# cw312_xc7A35t_fpga_io1.net
KiCad netlist of a schematic drawn in Altium Designer
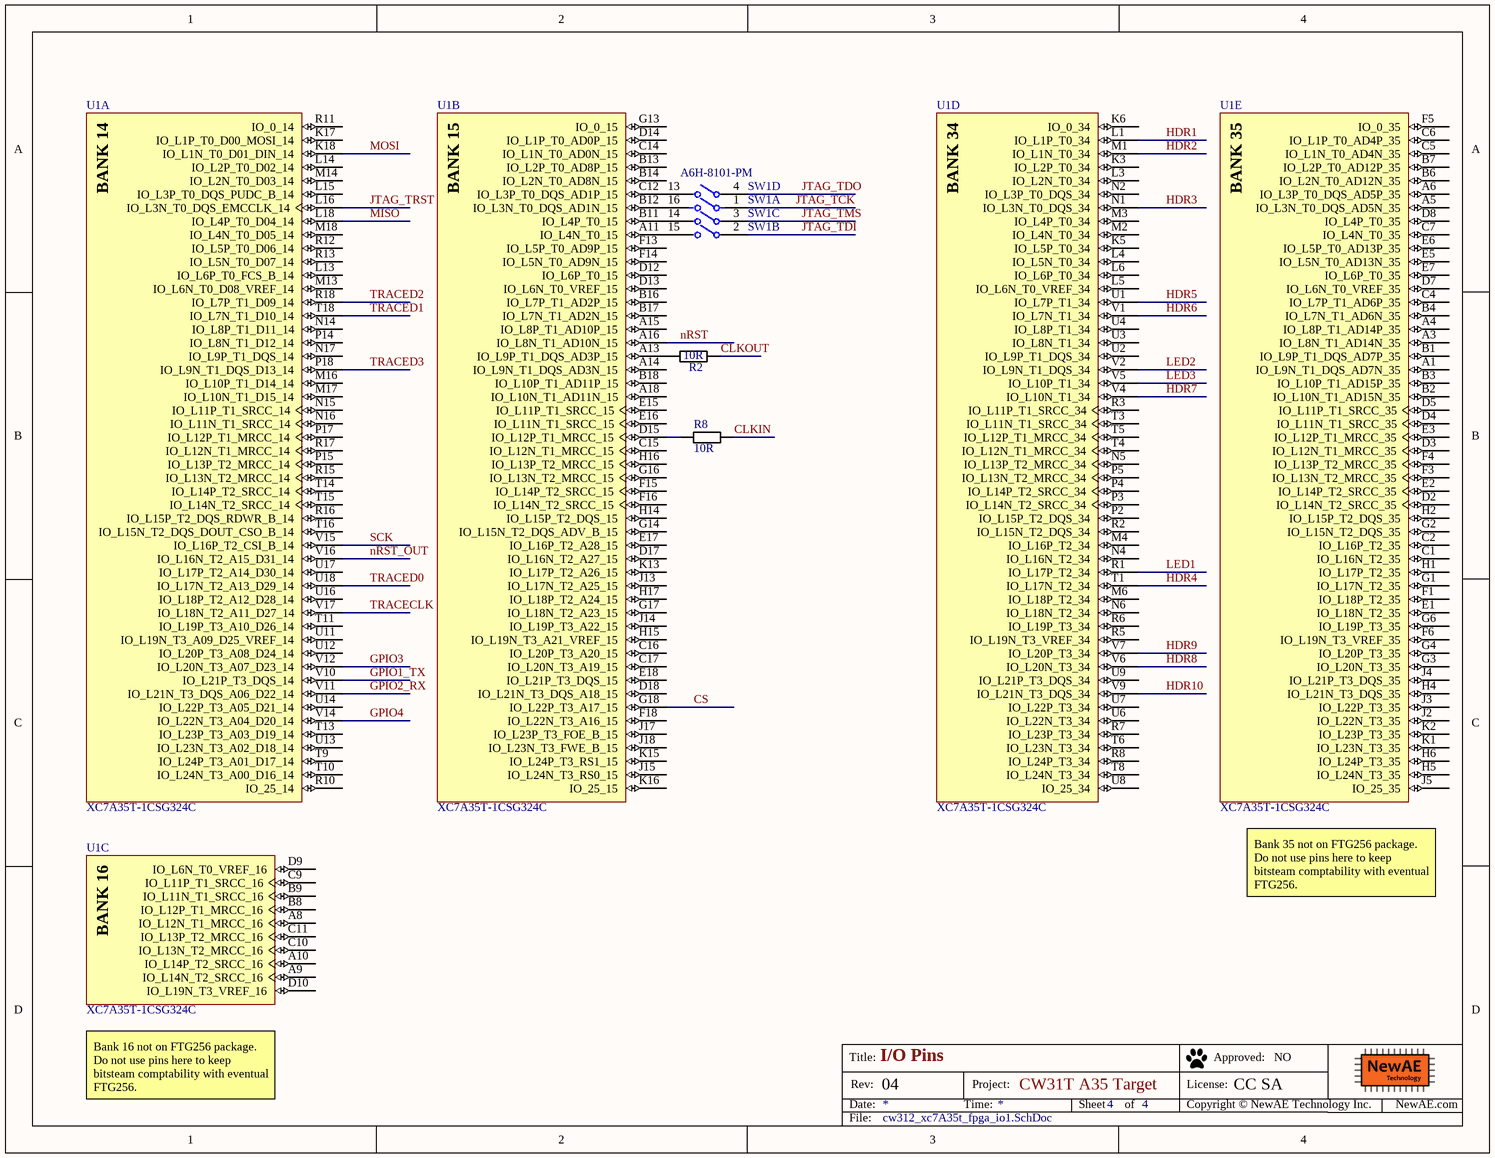
[diagram p0: cw312_xc7A35t_fpga_io1.SchDoc]

(export (version "E")
  (design (tool "Eeschema 10.0.6"))
  (components
    (comp (ref "R2")
      (value "10R")
      (footprint "RESC1608X55N")
      (description "10R res, 0603, 1%, 1/10W")
      (fields (field (name "PART NUMBER") "RCHIP-10R-0603") (field (name "TOLERANCE") "1%"))
      (libsource (lib "NewAE_AltiumLib") (part "RES-EU"))
    )
    (comp (ref "R8")
      (value "10R")
      (footprint "RESC1608X55N")
      (description "10R res, 0603, 1%, 1/10W")
      (fields (field (name "PART NUMBER") "RCHIP-10R-0603") (field (name "TOLERANCE") "1%"))
      (libsource (lib "NewAE_AltiumLib") (part "RES-EU"))
    )
    (comp (ref "SW1")
      (value "A6H-8101-PM")
      (footprint "FP-A6H-8101-PM-MFG")
      (description "SWITCH SLIDE DIP SPST 25MA 24V")
      (libsource (lib "Altium Content Vault") (part "b1c630a2f26d6f55c46b66680387f8a"))
    )
    (comp (ref "U1")
      (value "XC7A35T-1CSG324C")
      (footprint "CSG324")
      (description "Artix-7 FPGA, 210 User I/Os, 0 GTP, 324-Ball BGA, Speed Grade 1, Commercial Grade, Pb-Free")
      (fields (field (name "MANUFACTURER") "Xilinx"))
      (libsource (lib "Altium Content Vault") (part "XLNX-XC7A35T-CSG324"))
    )
  )
  (nets
    (net (code "1") (name "/CLKIN") (class "Default")
      (node (ref "R8") (pin "1") (pinfunction "1_1") (pintype "passive"))
    )
    (net (code "2") (name "/CLKOUT") (class "Default")
      (node (ref "R2") (pin "1") (pinfunction "1_1") (pintype "passive"))
    )
    (net (code "3") (name "/CS") (class "Default")
      (node (ref "U1") (pin "G18") (pinfunction "IO_L22P_T3_A17_15_G18") (pintype "bidirectional"))
    )
    (net (code "4") (name "/GPIO1_TX") (class "Default")
      (node (ref "U1") (pin "V10") (pinfunction "IO_L21P_T3_DQS_14_V10") (pintype "bidirectional"))
    )
    (net (code "5") (name "/GPIO2_RX") (class "Default")
      (node (ref "U1") (pin "V11") (pinfunction "IO_L21N_T3_DQS_A06_D22_14_V11") (pintype "bidirectional"))
    )
    (net (code "6") (name "/GPIO3") (class "Default")
      (node (ref "U1") (pin "V12") (pinfunction "IO_L20N_T3_A07_D23_14_V12") (pintype "bidirectional"))
    )
    (net (code "7") (name "/GPIO4") (class "Default")
      (node (ref "U1") (pin "V14") (pinfunction "IO_L22N_T3_A04_D20_14_V14") (pintype "bidirectional"))
    )
    (net (code "8") (name "/HDR1") (class "Default")
      (node (ref "U1") (pin "L1") (pinfunction "IO_L1P_T0_34_L1") (pintype "bidirectional"))
    )
    (net (code "9") (name "/HDR2") (class "Default")
      (node (ref "U1") (pin "M1") (pinfunction "IO_L1N_T0_34_M1") (pintype "bidirectional"))
    )
    (net (code "10") (name "/HDR3") (class "Default")
      (node (ref "U1") (pin "N1") (pinfunction "IO_L3N_T0_DQS_34_N1") (pintype "bidirectional"))
    )
    (net (code "11") (name "/HDR4") (class "Default")
      (node (ref "U1") (pin "T1") (pinfunction "IO_L17N_T2_34_T1") (pintype "bidirectional"))
    )
    (net (code "12") (name "/HDR5") (class "Default")
      (node (ref "U1") (pin "U1") (pinfunction "IO_L7P_T1_34_U1") (pintype "bidirectional"))
    )
    (net (code "13") (name "/HDR6") (class "Default")
      (node (ref "U1") (pin "V1") (pinfunction "IO_L7N_T1_34_V1") (pintype "bidirectional"))
    )
    (net (code "14") (name "/HDR7") (class "Default")
      (node (ref "U1") (pin "V4") (pinfunction "IO_L10N_T1_34_V4") (pintype "bidirectional"))
    )
    (net (code "15") (name "/HDR8") (class "Default")
      (node (ref "U1") (pin "V6") (pinfunction "IO_L20N_T3_34_V6") (pintype "bidirectional"))
    )
    (net (code "16") (name "/HDR9") (class "Default")
      (node (ref "U1") (pin "V7") (pinfunction "IO_L20P_T3_34_V7") (pintype "bidirectional"))
    )
    (net (code "17") (name "/HDR10") (class "Default")
      (node (ref "U1") (pin "V9") (pinfunction "IO_L21N_T3_DQS_34_V9") (pintype "bidirectional"))
    )
    (net (code "18") (name "/JTAG_TCK") (class "Default")
      (node (ref "SW1") (pin "1") (pinfunction "1_1") (pintype "passive"))
    )
    (net (code "19") (name "/JTAG_TDI") (class "Default")
      (node (ref "SW1") (pin "2") (pinfunction "2_2") (pintype "passive"))
    )
    (net (code "20") (name "/JTAG_TDO") (class "Default")
      (node (ref "SW1") (pin "4") (pinfunction "4_4") (pintype "passive"))
    )
    (net (code "21") (name "/JTAG_TMS") (class "Default")
      (node (ref "SW1") (pin "3") (pinfunction "3_3") (pintype "passive"))
    )
    (net (code "22") (name "/JTAG_TRST") (class "Default")
      (node (ref "U1") (pin "L16") (pinfunction "IO_L3N_T0_DQS_EMCCLK_14_L16") (pintype "bidirectional"))
    )
    (net (code "23") (name "/LED1") (class "Default")
      (node (ref "U1") (pin "R1") (pinfunction "IO_L17P_T2_34_R1") (pintype "bidirectional"))
    )
    (net (code "24") (name "/LED2") (class "Default")
      (node (ref "U1") (pin "V2") (pinfunction "IO_L9N_T1_DQS_34_V2") (pintype "bidirectional"))
    )
    (net (code "25") (name "/LED3") (class "Default")
      (node (ref "U1") (pin "V5") (pinfunction "IO_L10P_T1_34_V5") (pintype "bidirectional"))
    )
    (net (code "26") (name "/MISO") (class "Default")
      (node (ref "U1") (pin "L18") (pinfunction "IO_L4P_T0_D04_14_L18") (pintype "bidirectional"))
    )
    (net (code "27") (name "/MOSI") (class "Default")
      (node (ref "U1") (pin "K18") (pinfunction "IO_L1N_T0_D01_DIN_14_K18") (pintype "bidirectional"))
    )
    (net (code "28") (name "/SCK") (class "Default")
      (node (ref "U1") (pin "V15") (pinfunction "IO_L16P_T2_CSI_B_14_V15") (pintype "bidirectional"))
    )
    (net (code "29") (name "/TRACECLK") (class "Default")
      (node (ref "U1") (pin "V17") (pinfunction "IO_L18N_T2_A11_D27_14_V17") (pintype "bidirectional"))
    )
    (net (code "30") (name "/TRACED0") (class "Default")
      (node (ref "U1") (pin "U18") (pinfunction "IO_L17N_T2_A13_D29_14_U18") (pintype "bidirectional"))
    )
    (net (code "31") (name "/TRACED1") (class "Default")
      (node (ref "U1") (pin "T18") (pinfunction "IO_L7N_T1_D10_14_T18") (pintype "bidirectional"))
    )
    (net (code "32") (name "/TRACED2") (class "Default")
      (node (ref "U1") (pin "R18") (pinfunction "IO_L7P_T1_D09_14_R18") (pintype "bidirectional"))
    )
    (net (code "33") (name "/TRACED3") (class "Default")
      (node (ref "U1") (pin "P18") (pinfunction "IO_L9N_T1_DQS_D13_14_P18") (pintype "bidirectional"))
    )
    (net (code "34") (name "/nRST") (class "Default")
      (node (ref "U1") (pin "A16") (pinfunction "IO_L8N_T1_AD10N_15_A16") (pintype "bidirectional"))
    )
    (net (code "35") (name "/nRST_OUT") (class "Default")
      (node (ref "U1") (pin "V16") (pinfunction "IO_L16N_T2_A15_D31_14_V16") (pintype "bidirectional"))
    )
    (net (code "36") (name "Net-(U1B-IO_L3N_T0_DQS_AD1N_15)") (class "Default")
      (node (ref "SW1") (pin "16") (pinfunction "16_16") (pintype "passive"))
      (node (ref "U1") (pin "B12") (pinfunction "IO_L3N_T0_DQS_AD1N_15_B12") (pintype "bidirectional"))
    )
    (net (code "37") (name "Net-(U1B-IO_L3P_T0_DQS_AD1P_15)") (class "Default")
      (node (ref "SW1") (pin "13") (pinfunction "13_13") (pintype "passive"))
      (node (ref "U1") (pin "C12") (pinfunction "IO_L3P_T0_DQS_AD1P_15_C12") (pintype "bidirectional"))
    )
    (net (code "38") (name "Net-(U1B-IO_L4N_T0_15)") (class "Default")
      (node (ref "SW1") (pin "15") (pinfunction "15_15") (pintype "passive"))
      (node (ref "U1") (pin "A11") (pinfunction "IO_L4N_T0_15_A11") (pintype "bidirectional"))
    )
    (net (code "39") (name "Net-(U1B-IO_L4P_T0_15)") (class "Default")
      (node (ref "SW1") (pin "14") (pinfunction "14_14") (pintype "passive"))
      (node (ref "U1") (pin "B11") (pinfunction "IO_L4P_T0_15_B11") (pintype "bidirectional"))
    )
    (net (code "40") (name "Net-(U1B-IO_L9P_T1_DQS_AD3P_15)") (class "Default")
      (node (ref "R2") (pin "2") (pinfunction "2_2") (pintype "passive"))
      (node (ref "U1") (pin "A13") (pinfunction "IO_L9P_T1_DQS_AD3P_15_A13") (pintype "bidirectional"))
    )
    (net (code "41") (name "Net-(U1B-IO_L12P_T1_MRCC_15)") (class "Default")
      (node (ref "R8") (pin "2") (pinfunction "2_2") (pintype "passive"))
      (node (ref "U1") (pin "D15") (pinfunction "IO_L12P_T1_MRCC_15_D15") (pintype "bidirectional"))
    )
    (net (code "42") (name "unconnected-(U1A-IO_0_14-PadR11)") (class "Default")
      (node (ref "U1") (pin "R11") (pinfunction "IO_0_14_R11") (pintype "bidirectional"))
    )
    (net (code "43") (name "unconnected-(U1A-IO_25_14-PadR10)") (class "Default")
      (node (ref "U1") (pin "R10") (pinfunction "IO_25_14_R10") (pintype "bidirectional"))
    )
    (net (code "44") (name "unconnected-(U1A-IO_L1P_T0_D00_MOSI_14-PadK17)") (class "Default")
      (node (ref "U1") (pin "K17") (pinfunction "IO_L1P_T0_D00_MOSI_14_K17") (pintype "bidirectional"))
    )
    (net (code "45") (name "unconnected-(U1A-IO_L2N_T0_D03_14-PadM14)") (class "Default")
      (node (ref "U1") (pin "M14") (pinfunction "IO_L2N_T0_D03_14_M14") (pintype "bidirectional"))
    )
    (net (code "46") (name "unconnected-(U1A-IO_L2P_T0_D02_14-PadL14)") (class "Default")
      (node (ref "U1") (pin "L14") (pinfunction "IO_L2P_T0_D02_14_L14") (pintype "bidirectional"))
    )
    (net (code "47") (name "unconnected-(U1A-IO_L3P_T0_DQS_PUDC_B_14-PadL15)") (class "Default")
      (node (ref "U1") (pin "L15") (pinfunction "IO_L3P_T0_DQS_PUDC_B_14_L15") (pintype "bidirectional"))
    )
    (net (code "48") (name "unconnected-(U1A-IO_L4N_T0_D05_14-PadM18)") (class "Default")
      (node (ref "U1") (pin "M18") (pinfunction "IO_L4N_T0_D05_14_M18") (pintype "bidirectional"))
    )
    (net (code "49") (name "unconnected-(U1A-IO_L5N_T0_D07_14-PadR13)") (class "Default")
      (node (ref "U1") (pin "R13") (pinfunction "IO_L5N_T0_D07_14_R13") (pintype "bidirectional"))
    )
    (net (code "50") (name "unconnected-(U1A-IO_L5P_T0_D06_14-PadR12)") (class "Default")
      (node (ref "U1") (pin "R12") (pinfunction "IO_L5P_T0_D06_14_R12") (pintype "bidirectional"))
    )
    (net (code "51") (name "unconnected-(U1A-IO_L6N_T0_D08_VREF_14-PadM13)") (class "Default")
      (node (ref "U1") (pin "M13") (pinfunction "IO_L6N_T0_D08_VREF_14_M13") (pintype "bidirectional"))
    )
    (net (code "52") (name "unconnected-(U1A-IO_L6P_T0_FCS_B_14-PadL13)") (class "Default")
      (node (ref "U1") (pin "L13") (pinfunction "IO_L6P_T0_FCS_B_14_L13") (pintype "bidirectional"))
    )
    (net (code "53") (name "unconnected-(U1A-IO_L8N_T1_D12_14-PadP14)") (class "Default")
      (node (ref "U1") (pin "P14") (pinfunction "IO_L8N_T1_D12_14_P14") (pintype "bidirectional"))
    )
    (net (code "54") (name "unconnected-(U1A-IO_L8P_T1_D11_14-PadN14)") (class "Default")
      (node (ref "U1") (pin "N14") (pinfunction "IO_L8P_T1_D11_14_N14") (pintype "bidirectional"))
    )
    (net (code "55") (name "unconnected-(U1A-IO_L9P_T1_DQS_14-PadN17)") (class "Default")
      (node (ref "U1") (pin "N17") (pinfunction "IO_L9P_T1_DQS_14_N17") (pintype "bidirectional"))
    )
    (net (code "56") (name "unconnected-(U1A-IO_L10N_T1_D15_14-PadM17)") (class "Default")
      (node (ref "U1") (pin "M17") (pinfunction "IO_L10N_T1_D15_14_M17") (pintype "bidirectional"))
    )
    (net (code "57") (name "unconnected-(U1A-IO_L10P_T1_D14_14-PadM16)") (class "Default")
      (node (ref "U1") (pin "M16") (pinfunction "IO_L10P_T1_D14_14_M16") (pintype "bidirectional"))
    )
    (net (code "58") (name "unconnected-(U1A-IO_L11N_T1_SRCC_14-PadN16)") (class "Default")
      (node (ref "U1") (pin "N16") (pinfunction "IO_L11N_T1_SRCC_14_N16") (pintype "bidirectional"))
    )
    (net (code "59") (name "unconnected-(U1A-IO_L11P_T1_SRCC_14-PadN15)") (class "Default")
      (node (ref "U1") (pin "N15") (pinfunction "IO_L11P_T1_SRCC_14_N15") (pintype "bidirectional"))
    )
    (net (code "60") (name "unconnected-(U1A-IO_L12N_T1_MRCC_14-PadR17)") (class "Default")
      (node (ref "U1") (pin "R17") (pinfunction "IO_L12N_T1_MRCC_14_R17") (pintype "bidirectional"))
    )
    (net (code "61") (name "unconnected-(U1A-IO_L12P_T1_MRCC_14-PadP17)") (class "Default")
      (node (ref "U1") (pin "P17") (pinfunction "IO_L12P_T1_MRCC_14_P17") (pintype "bidirectional"))
    )
    (net (code "62") (name "unconnected-(U1A-IO_L13N_T2_MRCC_14-PadR15)") (class "Default")
      (node (ref "U1") (pin "R15") (pinfunction "IO_L13N_T2_MRCC_14_R15") (pintype "bidirectional"))
    )
    (net (code "63") (name "unconnected-(U1A-IO_L13P_T2_MRCC_14-PadP15)") (class "Default")
      (node (ref "U1") (pin "P15") (pinfunction "IO_L13P_T2_MRCC_14_P15") (pintype "bidirectional"))
    )
    (net (code "64") (name "unconnected-(U1A-IO_L14N_T2_SRCC_14-PadT15)") (class "Default")
      (node (ref "U1") (pin "T15") (pinfunction "IO_L14N_T2_SRCC_14_T15") (pintype "bidirectional"))
    )
    (net (code "65") (name "unconnected-(U1A-IO_L14P_T2_SRCC_14-PadT14)") (class "Default")
      (node (ref "U1") (pin "T14") (pinfunction "IO_L14P_T2_SRCC_14_T14") (pintype "bidirectional"))
    )
    (net (code "66") (name "unconnected-(U1A-IO_L15N_T2_DQS_DOUT_CSO_B_14-PadT16)") (class "Default")
      (node (ref "U1") (pin "T16") (pinfunction "IO_L15N_T2_DQS_DOUT_CSO_B_14_T16") (pintype "bidirectional"))
    )
    (net (code "67") (name "unconnected-(U1A-IO_L15P_T2_DQS_RDWR_B_14-PadR16)") (class "Default")
      (node (ref "U1") (pin "R16") (pinfunction "IO_L15P_T2_DQS_RDWR_B_14_R16") (pintype "bidirectional"))
    )
    (net (code "68") (name "unconnected-(U1A-IO_L17P_T2_A14_D30_14-PadU17)") (class "Default")
      (node (ref "U1") (pin "U17") (pinfunction "IO_L17P_T2_A14_D30_14_U17") (pintype "bidirectional"))
    )
    (net (code "69") (name "unconnected-(U1A-IO_L18P_T2_A12_D28_14-PadU16)") (class "Default")
      (node (ref "U1") (pin "U16") (pinfunction "IO_L18P_T2_A12_D28_14_U16") (pintype "bidirectional"))
    )
    (net (code "70") (name "unconnected-(U1A-IO_L19N_T3_A09_D25_VREF_14-PadU11)") (class "Default")
      (node (ref "U1") (pin "U11") (pinfunction "IO_L19N_T3_A09_D25_VREF_14_U11") (pintype "bidirectional"))
    )
    (net (code "71") (name "unconnected-(U1A-IO_L19P_T3_A10_D26_14-PadT11)") (class "Default")
      (node (ref "U1") (pin "T11") (pinfunction "IO_L19P_T3_A10_D26_14_T11") (pintype "bidirectional"))
    )
    (net (code "72") (name "unconnected-(U1A-IO_L20P_T3_A08_D24_14-PadU12)") (class "Default")
      (node (ref "U1") (pin "U12") (pinfunction "IO_L20P_T3_A08_D24_14_U12") (pintype "bidirectional"))
    )
    (net (code "73") (name "unconnected-(U1A-IO_L22P_T3_A05_D21_14-PadU14)") (class "Default")
      (node (ref "U1") (pin "U14") (pinfunction "IO_L22P_T3_A05_D21_14_U14") (pintype "bidirectional"))
    )
    (net (code "74") (name "unconnected-(U1A-IO_L23N_T3_A02_D18_14-PadU13)") (class "Default")
      (node (ref "U1") (pin "U13") (pinfunction "IO_L23N_T3_A02_D18_14_U13") (pintype "bidirectional"))
    )
    (net (code "75") (name "unconnected-(U1A-IO_L23P_T3_A03_D19_14-PadT13)") (class "Default")
      (node (ref "U1") (pin "T13") (pinfunction "IO_L23P_T3_A03_D19_14_T13") (pintype "bidirectional"))
    )
    (net (code "76") (name "unconnected-(U1A-IO_L24N_T3_A00_D16_14-PadT10)") (class "Default")
      (node (ref "U1") (pin "T10") (pinfunction "IO_L24N_T3_A00_D16_14_T10") (pintype "bidirectional"))
    )
    (net (code "77") (name "unconnected-(U1A-IO_L24P_T3_A01_D17_14-PadT9)") (class "Default")
      (node (ref "U1") (pin "T9") (pinfunction "IO_L24P_T3_A01_D17_14_T9") (pintype "bidirectional"))
    )
    (net (code "78") (name "unconnected-(U1B-IO_0_15-PadG13)") (class "Default")
      (node (ref "U1") (pin "G13") (pinfunction "IO_0_15_G13") (pintype "bidirectional"))
    )
    (net (code "79") (name "unconnected-(U1B-IO_25_15-PadK16)") (class "Default")
      (node (ref "U1") (pin "K16") (pinfunction "IO_25_15_K16") (pintype "bidirectional"))
    )
    (net (code "80") (name "unconnected-(U1B-IO_L1N_T0_AD0N_15-PadC14)") (class "Default")
      (node (ref "U1") (pin "C14") (pinfunction "IO_L1N_T0_AD0N_15_C14") (pintype "bidirectional"))
    )
    (net (code "81") (name "unconnected-(U1B-IO_L1P_T0_AD0P_15-PadD14)") (class "Default")
      (node (ref "U1") (pin "D14") (pinfunction "IO_L1P_T0_AD0P_15_D14") (pintype "bidirectional"))
    )
    (net (code "82") (name "unconnected-(U1B-IO_L2N_T0_AD8N_15-PadB14)") (class "Default")
      (node (ref "U1") (pin "B14") (pinfunction "IO_L2N_T0_AD8N_15_B14") (pintype "bidirectional"))
    )
    (net (code "83") (name "unconnected-(U1B-IO_L2P_T0_AD8P_15-PadB13)") (class "Default")
      (node (ref "U1") (pin "B13") (pinfunction "IO_L2P_T0_AD8P_15_B13") (pintype "bidirectional"))
    )
    (net (code "84") (name "unconnected-(U1B-IO_L5N_T0_AD9N_15-PadF14)") (class "Default")
      (node (ref "U1") (pin "F14") (pinfunction "IO_L5N_T0_AD9N_15_F14") (pintype "bidirectional"))
    )
    (net (code "85") (name "unconnected-(U1B-IO_L5P_T0_AD9P_15-PadF13)") (class "Default")
      (node (ref "U1") (pin "F13") (pinfunction "IO_L5P_T0_AD9P_15_F13") (pintype "bidirectional"))
    )
    (net (code "86") (name "unconnected-(U1B-IO_L6N_T0_VREF_15-PadD13)") (class "Default")
      (node (ref "U1") (pin "D13") (pinfunction "IO_L6N_T0_VREF_15_D13") (pintype "bidirectional"))
    )
    (net (code "87") (name "unconnected-(U1B-IO_L6P_T0_15-PadD12)") (class "Default")
      (node (ref "U1") (pin "D12") (pinfunction "IO_L6P_T0_15_D12") (pintype "bidirectional"))
    )
    (net (code "88") (name "unconnected-(U1B-IO_L7N_T1_AD2N_15-PadB17)") (class "Default")
      (node (ref "U1") (pin "B17") (pinfunction "IO_L7N_T1_AD2N_15_B17") (pintype "bidirectional"))
    )
    (net (code "89") (name "unconnected-(U1B-IO_L7P_T1_AD2P_15-PadB16)") (class "Default")
      (node (ref "U1") (pin "B16") (pinfunction "IO_L7P_T1_AD2P_15_B16") (pintype "bidirectional"))
    )
    (net (code "90") (name "unconnected-(U1B-IO_L8P_T1_AD10P_15-PadA15)") (class "Default")
      (node (ref "U1") (pin "A15") (pinfunction "IO_L8P_T1_AD10P_15_A15") (pintype "bidirectional"))
    )
    (net (code "91") (name "unconnected-(U1B-IO_L9N_T1_DQS_AD3N_15-PadA14)") (class "Default")
      (node (ref "U1") (pin "A14") (pinfunction "IO_L9N_T1_DQS_AD3N_15_A14") (pintype "bidirectional"))
    )
    (net (code "92") (name "unconnected-(U1B-IO_L10N_T1_AD11N_15-PadA18)") (class "Default")
      (node (ref "U1") (pin "A18") (pinfunction "IO_L10N_T1_AD11N_15_A18") (pintype "bidirectional"))
    )
    (net (code "93") (name "unconnected-(U1B-IO_L10P_T1_AD11P_15-PadB18)") (class "Default")
      (node (ref "U1") (pin "B18") (pinfunction "IO_L10P_T1_AD11P_15_B18") (pintype "bidirectional"))
    )
    (net (code "94") (name "unconnected-(U1B-IO_L11N_T1_SRCC_15-PadE16)") (class "Default")
      (node (ref "U1") (pin "E16") (pinfunction "IO_L11N_T1_SRCC_15_E16") (pintype "bidirectional"))
    )
    (net (code "95") (name "unconnected-(U1B-IO_L11P_T1_SRCC_15-PadE15)") (class "Default")
      (node (ref "U1") (pin "E15") (pinfunction "IO_L11P_T1_SRCC_15_E15") (pintype "bidirectional"))
    )
    (net (code "96") (name "unconnected-(U1B-IO_L12N_T1_MRCC_15-PadC15)") (class "Default")
      (node (ref "U1") (pin "C15") (pinfunction "IO_L12N_T1_MRCC_15_C15") (pintype "bidirectional"))
    )
    (net (code "97") (name "unconnected-(U1B-IO_L13N_T2_MRCC_15-PadG16)") (class "Default")
      (node (ref "U1") (pin "G16") (pinfunction "IO_L13N_T2_MRCC_15_G16") (pintype "bidirectional"))
    )
    (net (code "98") (name "unconnected-(U1B-IO_L13P_T2_MRCC_15-PadH16)") (class "Default")
      (node (ref "U1") (pin "H16") (pinfunction "IO_L13P_T2_MRCC_15_H16") (pintype "bidirectional"))
    )
    (net (code "99") (name "unconnected-(U1B-IO_L14N_T2_SRCC_15-PadF16)") (class "Default")
      (node (ref "U1") (pin "F16") (pinfunction "IO_L14N_T2_SRCC_15_F16") (pintype "bidirectional"))
    )
    (net (code "100") (name "unconnected-(U1B-IO_L14P_T2_SRCC_15-PadF15)") (class "Default")
      (node (ref "U1") (pin "F15") (pinfunction "IO_L14P_T2_SRCC_15_F15") (pintype "bidirectional"))
    )
    (net (code "101") (name "unconnected-(U1B-IO_L15N_T2_DQS_ADV_B_15-PadG14)") (class "Default")
      (node (ref "U1") (pin "G14") (pinfunction "IO_L15N_T2_DQS_ADV_B_15_G14") (pintype "bidirectional"))
    )
    (net (code "102") (name "unconnected-(U1B-IO_L15P_T2_DQS_15-PadH14)") (class "Default")
      (node (ref "U1") (pin "H14") (pinfunction "IO_L15P_T2_DQS_15_H14") (pintype "bidirectional"))
    )
    (net (code "103") (name "unconnected-(U1B-IO_L16N_T2_A27_15-PadD17)") (class "Default")
      (node (ref "U1") (pin "D17") (pinfunction "IO_L16N_T2_A27_15_D17") (pintype "bidirectional"))
    )
    (net (code "104") (name "unconnected-(U1B-IO_L16P_T2_A28_15-PadE17)") (class "Default")
      (node (ref "U1") (pin "E17") (pinfunction "IO_L16P_T2_A28_15_E17") (pintype "bidirectional"))
    )
    (net (code "105") (name "unconnected-(U1B-IO_L17N_T2_A25_15-PadJ13)") (class "Default")
      (node (ref "U1") (pin "J13") (pinfunction "IO_L17N_T2_A25_15_J13") (pintype "bidirectional"))
    )
    (net (code "106") (name "unconnected-(U1B-IO_L17P_T2_A26_15-PadK13)") (class "Default")
      (node (ref "U1") (pin "K13") (pinfunction "IO_L17P_T2_A26_15_K13") (pintype "bidirectional"))
    )
    (net (code "107") (name "unconnected-(U1B-IO_L18N_T2_A23_15-PadG17)") (class "Default")
      (node (ref "U1") (pin "G17") (pinfunction "IO_L18N_T2_A23_15_G17") (pintype "bidirectional"))
    )
    (net (code "108") (name "unconnected-(U1B-IO_L18P_T2_A24_15-PadH17)") (class "Default")
      (node (ref "U1") (pin "H17") (pinfunction "IO_L18P_T2_A24_15_H17") (pintype "bidirectional"))
    )
    (net (code "109") (name "unconnected-(U1B-IO_L19N_T3_A21_VREF_15-PadH15)") (class "Default")
      (node (ref "U1") (pin "H15") (pinfunction "IO_L19N_T3_A21_VREF_15_H15") (pintype "bidirectional"))
    )
    (net (code "110") (name "unconnected-(U1B-IO_L19P_T3_A22_15-PadJ14)") (class "Default")
      (node (ref "U1") (pin "J14") (pinfunction "IO_L19P_T3_A22_15_J14") (pintype "bidirectional"))
    )
    (net (code "111") (name "unconnected-(U1B-IO_L20N_T3_A19_15-PadC17)") (class "Default")
      (node (ref "U1") (pin "C17") (pinfunction "IO_L20N_T3_A19_15_C17") (pintype "bidirectional"))
    )
    (net (code "112") (name "unconnected-(U1B-IO_L20P_T3_A20_15-PadC16)") (class "Default")
      (node (ref "U1") (pin "C16") (pinfunction "IO_L20P_T3_A20_15_C16") (pintype "bidirectional"))
    )
    (net (code "113") (name "unconnected-(U1B-IO_L21N_T3_DQS_A18_15-PadD18)") (class "Default")
      (node (ref "U1") (pin "D18") (pinfunction "IO_L21N_T3_DQS_A18_15_D18") (pintype "bidirectional"))
    )
    (net (code "114") (name "unconnected-(U1B-IO_L21P_T3_DQS_15-PadE18)") (class "Default")
      (node (ref "U1") (pin "E18") (pinfunction "IO_L21P_T3_DQS_15_E18") (pintype "bidirectional"))
    )
    (net (code "115") (name "unconnected-(U1B-IO_L22N_T3_A16_15-PadF18)") (class "Default")
      (node (ref "U1") (pin "F18") (pinfunction "IO_L22N_T3_A16_15_F18") (pintype "bidirectional"))
    )
    (net (code "116") (name "unconnected-(U1B-IO_L23N_T3_FWE_B_15-PadJ18)") (class "Default")
      (node (ref "U1") (pin "J18") (pinfunction "IO_L23N_T3_FWE_B_15_J18") (pintype "bidirectional"))
    )
    (net (code "117") (name "unconnected-(U1B-IO_L23P_T3_FOE_B_15-PadJ17)") (class "Default")
      (node (ref "U1") (pin "J17") (pinfunction "IO_L23P_T3_FOE_B_15_J17") (pintype "bidirectional"))
    )
    (net (code "118") (name "unconnected-(U1B-IO_L24N_T3_RS0_15-PadJ15)") (class "Default")
      (node (ref "U1") (pin "J15") (pinfunction "IO_L24N_T3_RS0_15_J15") (pintype "bidirectional"))
    )
    (net (code "119") (name "unconnected-(U1B-IO_L24P_T3_RS1_15-PadK15)") (class "Default")
      (node (ref "U1") (pin "K15") (pinfunction "IO_L24P_T3_RS1_15_K15") (pintype "bidirectional"))
    )
    (net (code "120") (name "unconnected-(U1C-IO_L6N_T0_VREF_16-PadD9)") (class "Default")
      (node (ref "U1") (pin "D9") (pinfunction "IO_L6N_T0_VREF_16_D9") (pintype "bidirectional"))
    )
    (net (code "121") (name "unconnected-(U1C-IO_L11N_T1_SRCC_16-PadB9)") (class "Default")
      (node (ref "U1") (pin "B9") (pinfunction "IO_L11N_T1_SRCC_16_B9") (pintype "bidirectional"))
    )
    (net (code "122") (name "unconnected-(U1C-IO_L11P_T1_SRCC_16-PadC9)") (class "Default")
      (node (ref "U1") (pin "C9") (pinfunction "IO_L11P_T1_SRCC_16_C9") (pintype "bidirectional"))
    )
    (net (code "123") (name "unconnected-(U1C-IO_L12N_T1_MRCC_16-PadA8)") (class "Default")
      (node (ref "U1") (pin "A8") (pinfunction "IO_L12N_T1_MRCC_16_A8") (pintype "bidirectional"))
    )
    (net (code "124") (name "unconnected-(U1C-IO_L12P_T1_MRCC_16-PadB8)") (class "Default")
      (node (ref "U1") (pin "B8") (pinfunction "IO_L12P_T1_MRCC_16_B8") (pintype "bidirectional"))
    )
    (net (code "125") (name "unconnected-(U1C-IO_L13N_T2_MRCC_16-PadC10)") (class "Default")
      (node (ref "U1") (pin "C10") (pinfunction "IO_L13N_T2_MRCC_16_C10") (pintype "bidirectional"))
    )
    (net (code "126") (name "unconnected-(U1C-IO_L13P_T2_MRCC_16-PadC11)") (class "Default")
      (node (ref "U1") (pin "C11") (pinfunction "IO_L13P_T2_MRCC_16_C11") (pintype "bidirectional"))
    )
    (net (code "127") (name "unconnected-(U1C-IO_L14N_T2_SRCC_16-PadA9)") (class "Default")
      (node (ref "U1") (pin "A9") (pinfunction "IO_L14N_T2_SRCC_16_A9") (pintype "bidirectional"))
    )
    (net (code "128") (name "unconnected-(U1C-IO_L14P_T2_SRCC_16-PadA10)") (class "Default")
      (node (ref "U1") (pin "A10") (pinfunction "IO_L14P_T2_SRCC_16_A10") (pintype "bidirectional"))
    )
    (net (code "129") (name "unconnected-(U1C-IO_L19N_T3_VREF_16-PadD10)") (class "Default")
      (node (ref "U1") (pin "D10") (pinfunction "IO_L19N_T3_VREF_16_D10") (pintype "bidirectional"))
    )
    (net (code "130") (name "unconnected-(U1D-IO_0_34-PadK6)") (class "Default")
      (node (ref "U1") (pin "K6") (pinfunction "IO_0_34_K6") (pintype "bidirectional"))
    )
    (net (code "131") (name "unconnected-(U1D-IO_25_34-PadU8)") (class "Default")
      (node (ref "U1") (pin "U8") (pinfunction "IO_25_34_U8") (pintype "bidirectional"))
    )
    (net (code "132") (name "unconnected-(U1D-IO_L2N_T0_34-PadL3)") (class "Default")
      (node (ref "U1") (pin "L3") (pinfunction "IO_L2N_T0_34_L3") (pintype "bidirectional"))
    )
    (net (code "133") (name "unconnected-(U1D-IO_L2P_T0_34-PadK3)") (class "Default")
      (node (ref "U1") (pin "K3") (pinfunction "IO_L2P_T0_34_K3") (pintype "bidirectional"))
    )
    (net (code "134") (name "unconnected-(U1D-IO_L3P_T0_DQS_34-PadN2)") (class "Default")
      (node (ref "U1") (pin "N2") (pinfunction "IO_L3P_T0_DQS_34_N2") (pintype "bidirectional"))
    )
    (net (code "135") (name "unconnected-(U1D-IO_L4N_T0_34-PadM2)") (class "Default")
      (node (ref "U1") (pin "M2") (pinfunction "IO_L4N_T0_34_M2") (pintype "bidirectional"))
    )
    (net (code "136") (name "unconnected-(U1D-IO_L4P_T0_34-PadM3)") (class "Default")
      (node (ref "U1") (pin "M3") (pinfunction "IO_L4P_T0_34_M3") (pintype "bidirectional"))
    )
    (net (code "137") (name "unconnected-(U1D-IO_L5N_T0_34-PadL4)") (class "Default")
      (node (ref "U1") (pin "L4") (pinfunction "IO_L5N_T0_34_L4") (pintype "bidirectional"))
    )
    (net (code "138") (name "unconnected-(U1D-IO_L5P_T0_34-PadK5)") (class "Default")
      (node (ref "U1") (pin "K5") (pinfunction "IO_L5P_T0_34_K5") (pintype "bidirectional"))
    )
    (net (code "139") (name "unconnected-(U1D-IO_L6N_T0_VREF_34-PadL5)") (class "Default")
      (node (ref "U1") (pin "L5") (pinfunction "IO_L6N_T0_VREF_34_L5") (pintype "bidirectional"))
    )
    (net (code "140") (name "unconnected-(U1D-IO_L6P_T0_34-PadL6)") (class "Default")
      (node (ref "U1") (pin "L6") (pinfunction "IO_L6P_T0_34_L6") (pintype "bidirectional"))
    )
    (net (code "141") (name "unconnected-(U1D-IO_L8N_T1_34-PadU3)") (class "Default")
      (node (ref "U1") (pin "U3") (pinfunction "IO_L8N_T1_34_U3") (pintype "bidirectional"))
    )
    (net (code "142") (name "unconnected-(U1D-IO_L8P_T1_34-PadU4)") (class "Default")
      (node (ref "U1") (pin "U4") (pinfunction "IO_L8P_T1_34_U4") (pintype "bidirectional"))
    )
    (net (code "143") (name "unconnected-(U1D-IO_L9P_T1_DQS_34-PadU2)") (class "Default")
      (node (ref "U1") (pin "U2") (pinfunction "IO_L9P_T1_DQS_34_U2") (pintype "bidirectional"))
    )
    (net (code "144") (name "unconnected-(U1D-IO_L11N_T1_SRCC_34-PadT3)") (class "Default")
      (node (ref "U1") (pin "T3") (pinfunction "IO_L11N_T1_SRCC_34_T3") (pintype "bidirectional"))
    )
    (net (code "145") (name "unconnected-(U1D-IO_L11P_T1_SRCC_34-PadR3)") (class "Default")
      (node (ref "U1") (pin "R3") (pinfunction "IO_L11P_T1_SRCC_34_R3") (pintype "bidirectional"))
    )
    (net (code "146") (name "unconnected-(U1D-IO_L12N_T1_MRCC_34-PadT4)") (class "Default")
      (node (ref "U1") (pin "T4") (pinfunction "IO_L12N_T1_MRCC_34_T4") (pintype "bidirectional"))
    )
    (net (code "147") (name "unconnected-(U1D-IO_L12P_T1_MRCC_34-PadT5)") (class "Default")
      (node (ref "U1") (pin "T5") (pinfunction "IO_L12P_T1_MRCC_34_T5") (pintype "bidirectional"))
    )
    (net (code "148") (name "unconnected-(U1D-IO_L13N_T2_MRCC_34-PadP5)") (class "Default")
      (node (ref "U1") (pin "P5") (pinfunction "IO_L13N_T2_MRCC_34_P5") (pintype "bidirectional"))
    )
    (net (code "149") (name "unconnected-(U1D-IO_L13P_T2_MRCC_34-PadN5)") (class "Default")
      (node (ref "U1") (pin "N5") (pinfunction "IO_L13P_T2_MRCC_34_N5") (pintype "bidirectional"))
    )
    (net (code "150") (name "unconnected-(U1D-IO_L14N_T2_SRCC_34-PadP3)") (class "Default")
      (node (ref "U1") (pin "P3") (pinfunction "IO_L14N_T2_SRCC_34_P3") (pintype "bidirectional"))
    )
    (net (code "151") (name "unconnected-(U1D-IO_L14P_T2_SRCC_34-PadP4)") (class "Default")
      (node (ref "U1") (pin "P4") (pinfunction "IO_L14P_T2_SRCC_34_P4") (pintype "bidirectional"))
    )
    (net (code "152") (name "unconnected-(U1D-IO_L15N_T2_DQS_34-PadR2)") (class "Default")
      (node (ref "U1") (pin "R2") (pinfunction "IO_L15N_T2_DQS_34_R2") (pintype "bidirectional"))
    )
    (net (code "153") (name "unconnected-(U1D-IO_L15P_T2_DQS_34-PadP2)") (class "Default")
      (node (ref "U1") (pin "P2") (pinfunction "IO_L15P_T2_DQS_34_P2") (pintype "bidirectional"))
    )
    (net (code "154") (name "unconnected-(U1D-IO_L16N_T2_34-PadN4)") (class "Default")
      (node (ref "U1") (pin "N4") (pinfunction "IO_L16N_T2_34_N4") (pintype "bidirectional"))
    )
    (net (code "155") (name "unconnected-(U1D-IO_L16P_T2_34-PadM4)") (class "Default")
      (node (ref "U1") (pin "M4") (pinfunction "IO_L16P_T2_34_M4") (pintype "bidirectional"))
    )
    (net (code "156") (name "unconnected-(U1D-IO_L18N_T2_34-PadN6)") (class "Default")
      (node (ref "U1") (pin "N6") (pinfunction "IO_L18N_T2_34_N6") (pintype "bidirectional"))
    )
    (net (code "157") (name "unconnected-(U1D-IO_L18P_T2_34-PadM6)") (class "Default")
      (node (ref "U1") (pin "M6") (pinfunction "IO_L18P_T2_34_M6") (pintype "bidirectional"))
    )
    (net (code "158") (name "unconnected-(U1D-IO_L19N_T3_VREF_34-PadR5)") (class "Default")
      (node (ref "U1") (pin "R5") (pinfunction "IO_L19N_T3_VREF_34_R5") (pintype "bidirectional"))
    )
    (net (code "159") (name "unconnected-(U1D-IO_L19P_T3_34-PadR6)") (class "Default")
      (node (ref "U1") (pin "R6") (pinfunction "IO_L19P_T3_34_R6") (pintype "bidirectional"))
    )
    (net (code "160") (name "unconnected-(U1D-IO_L21P_T3_DQS_34-PadU9)") (class "Default")
      (node (ref "U1") (pin "U9") (pinfunction "IO_L21P_T3_DQS_34_U9") (pintype "bidirectional"))
    )
    (net (code "161") (name "unconnected-(U1D-IO_L22N_T3_34-PadU6)") (class "Default")
      (node (ref "U1") (pin "U6") (pinfunction "IO_L22N_T3_34_U6") (pintype "bidirectional"))
    )
    (net (code "162") (name "unconnected-(U1D-IO_L22P_T3_34-PadU7)") (class "Default")
      (node (ref "U1") (pin "U7") (pinfunction "IO_L22P_T3_34_U7") (pintype "bidirectional"))
    )
    (net (code "163") (name "unconnected-(U1D-IO_L23N_T3_34-PadT6)") (class "Default")
      (node (ref "U1") (pin "T6") (pinfunction "IO_L23N_T3_34_T6") (pintype "bidirectional"))
    )
    (net (code "164") (name "unconnected-(U1D-IO_L23P_T3_34-PadR7)") (class "Default")
      (node (ref "U1") (pin "R7") (pinfunction "IO_L23P_T3_34_R7") (pintype "bidirectional"))
    )
    (net (code "165") (name "unconnected-(U1D-IO_L24N_T3_34-PadT8)") (class "Default")
      (node (ref "U1") (pin "T8") (pinfunction "IO_L24N_T3_34_T8") (pintype "bidirectional"))
    )
    (net (code "166") (name "unconnected-(U1D-IO_L24P_T3_34-PadR8)") (class "Default")
      (node (ref "U1") (pin "R8") (pinfunction "IO_L24P_T3_34_R8") (pintype "bidirectional"))
    )
    (net (code "167") (name "unconnected-(U1E-IO_0_35-PadF5)") (class "Default")
      (node (ref "U1") (pin "F5") (pinfunction "IO_0_35_F5") (pintype "bidirectional"))
    )
    (net (code "168") (name "unconnected-(U1E-IO_25_35-PadJ5)") (class "Default")
      (node (ref "U1") (pin "J5") (pinfunction "IO_25_35_J5") (pintype "bidirectional"))
    )
    (net (code "169") (name "unconnected-(U1E-IO_L1N_T0_AD4N_35-PadC5)") (class "Default")
      (node (ref "U1") (pin "C5") (pinfunction "IO_L1N_T0_AD4N_35_C5") (pintype "bidirectional"))
    )
    (net (code "170") (name "unconnected-(U1E-IO_L1P_T0_AD4P_35-PadC6)") (class "Default")
      (node (ref "U1") (pin "C6") (pinfunction "IO_L1P_T0_AD4P_35_C6") (pintype "bidirectional"))
    )
    (net (code "171") (name "unconnected-(U1E-IO_L2N_T0_AD12N_35-PadB6)") (class "Default")
      (node (ref "U1") (pin "B6") (pinfunction "IO_L2N_T0_AD12N_35_B6") (pintype "bidirectional"))
    )
    (net (code "172") (name "unconnected-(U1E-IO_L2P_T0_AD12P_35-PadB7)") (class "Default")
      (node (ref "U1") (pin "B7") (pinfunction "IO_L2P_T0_AD12P_35_B7") (pintype "bidirectional"))
    )
    (net (code "173") (name "unconnected-(U1E-IO_L3N_T0_DQS_AD5N_35-PadA5)") (class "Default")
      (node (ref "U1") (pin "A5") (pinfunction "IO_L3N_T0_DQS_AD5N_35_A5") (pintype "bidirectional"))
    )
    (net (code "174") (name "unconnected-(U1E-IO_L3P_T0_DQS_AD5P_35-PadA6)") (class "Default")
      (node (ref "U1") (pin "A6") (pinfunction "IO_L3P_T0_DQS_AD5P_35_A6") (pintype "bidirectional"))
    )
    (net (code "175") (name "unconnected-(U1E-IO_L4N_T0_35-PadC7)") (class "Default")
      (node (ref "U1") (pin "C7") (pinfunction "IO_L4N_T0_35_C7") (pintype "bidirectional"))
    )
    (net (code "176") (name "unconnected-(U1E-IO_L4P_T0_35-PadD8)") (class "Default")
      (node (ref "U1") (pin "D8") (pinfunction "IO_L4P_T0_35_D8") (pintype "bidirectional"))
    )
    (net (code "177") (name "unconnected-(U1E-IO_L5N_T0_AD13N_35-PadE5)") (class "Default")
      (node (ref "U1") (pin "E5") (pinfunction "IO_L5N_T0_AD13N_35_E5") (pintype "bidirectional"))
    )
    (net (code "178") (name "unconnected-(U1E-IO_L5P_T0_AD13P_35-PadE6)") (class "Default")
      (node (ref "U1") (pin "E6") (pinfunction "IO_L5P_T0_AD13P_35_E6") (pintype "bidirectional"))
    )
    (net (code "179") (name "unconnected-(U1E-IO_L6N_T0_VREF_35-PadD7)") (class "Default")
      (node (ref "U1") (pin "D7") (pinfunction "IO_L6N_T0_VREF_35_D7") (pintype "bidirectional"))
    )
    (net (code "180") (name "unconnected-(U1E-IO_L6P_T0_35-PadE7)") (class "Default")
      (node (ref "U1") (pin "E7") (pinfunction "IO_L6P_T0_35_E7") (pintype "bidirectional"))
    )
    (net (code "181") (name "unconnected-(U1E-IO_L7N_T1_AD6N_35-PadB4)") (class "Default")
      (node (ref "U1") (pin "B4") (pinfunction "IO_L7N_T1_AD6N_35_B4") (pintype "bidirectional"))
    )
    (net (code "182") (name "unconnected-(U1E-IO_L7P_T1_AD6P_35-PadC4)") (class "Default")
      (node (ref "U1") (pin "C4") (pinfunction "IO_L7P_T1_AD6P_35_C4") (pintype "bidirectional"))
    )
    (net (code "183") (name "unconnected-(U1E-IO_L8N_T1_AD14N_35-PadA3)") (class "Default")
      (node (ref "U1") (pin "A3") (pinfunction "IO_L8N_T1_AD14N_35_A3") (pintype "bidirectional"))
    )
    (net (code "184") (name "unconnected-(U1E-IO_L8P_T1_AD14P_35-PadA4)") (class "Default")
      (node (ref "U1") (pin "A4") (pinfunction "IO_L8P_T1_AD14P_35_A4") (pintype "bidirectional"))
    )
    (net (code "185") (name "unconnected-(U1E-IO_L9N_T1_DQS_AD7N_35-PadA1)") (class "Default")
      (node (ref "U1") (pin "A1") (pinfunction "IO_L9N_T1_DQS_AD7N_35_A1") (pintype "bidirectional"))
    )
    (net (code "186") (name "unconnected-(U1E-IO_L9P_T1_DQS_AD7P_35-PadB1)") (class "Default")
      (node (ref "U1") (pin "B1") (pinfunction "IO_L9P_T1_DQS_AD7P_35_B1") (pintype "bidirectional"))
    )
    (net (code "187") (name "unconnected-(U1E-IO_L10N_T1_AD15N_35-PadB2)") (class "Default")
      (node (ref "U1") (pin "B2") (pinfunction "IO_L10N_T1_AD15N_35_B2") (pintype "bidirectional"))
    )
    (net (code "188") (name "unconnected-(U1E-IO_L10P_T1_AD15P_35-PadB3)") (class "Default")
      (node (ref "U1") (pin "B3") (pinfunction "IO_L10P_T1_AD15P_35_B3") (pintype "bidirectional"))
    )
    (net (code "189") (name "unconnected-(U1E-IO_L11N_T1_SRCC_35-PadD4)") (class "Default")
      (node (ref "U1") (pin "D4") (pinfunction "IO_L11N_T1_SRCC_35_D4") (pintype "bidirectional"))
    )
    (net (code "190") (name "unconnected-(U1E-IO_L11P_T1_SRCC_35-PadD5)") (class "Default")
      (node (ref "U1") (pin "D5") (pinfunction "IO_L11P_T1_SRCC_35_D5") (pintype "bidirectional"))
    )
    (net (code "191") (name "unconnected-(U1E-IO_L12N_T1_MRCC_35-PadD3)") (class "Default")
      (node (ref "U1") (pin "D3") (pinfunction "IO_L12N_T1_MRCC_35_D3") (pintype "bidirectional"))
    )
    (net (code "192") (name "unconnected-(U1E-IO_L12P_T1_MRCC_35-PadE3)") (class "Default")
      (node (ref "U1") (pin "E3") (pinfunction "IO_L12P_T1_MRCC_35_E3") (pintype "bidirectional"))
    )
    (net (code "193") (name "unconnected-(U1E-IO_L13N_T2_MRCC_35-PadF3)") (class "Default")
      (node (ref "U1") (pin "F3") (pinfunction "IO_L13N_T2_MRCC_35_F3") (pintype "bidirectional"))
    )
    (net (code "194") (name "unconnected-(U1E-IO_L13P_T2_MRCC_35-PadF4)") (class "Default")
      (node (ref "U1") (pin "F4") (pinfunction "IO_L13P_T2_MRCC_35_F4") (pintype "bidirectional"))
    )
    (net (code "195") (name "unconnected-(U1E-IO_L14N_T2_SRCC_35-PadD2)") (class "Default")
      (node (ref "U1") (pin "D2") (pinfunction "IO_L14N_T2_SRCC_35_D2") (pintype "bidirectional"))
    )
    (net (code "196") (name "unconnected-(U1E-IO_L14P_T2_SRCC_35-PadE2)") (class "Default")
      (node (ref "U1") (pin "E2") (pinfunction "IO_L14P_T2_SRCC_35_E2") (pintype "bidirectional"))
    )
    (net (code "197") (name "unconnected-(U1E-IO_L15N_T2_DQS_35-PadG2)") (class "Default")
      (node (ref "U1") (pin "G2") (pinfunction "IO_L15N_T2_DQS_35_G2") (pintype "bidirectional"))
    )
    (net (code "198") (name "unconnected-(U1E-IO_L15P_T2_DQS_35-PadH2)") (class "Default")
      (node (ref "U1") (pin "H2") (pinfunction "IO_L15P_T2_DQS_35_H2") (pintype "bidirectional"))
    )
    (net (code "199") (name "unconnected-(U1E-IO_L16N_T2_35-PadC1)") (class "Default")
      (node (ref "U1") (pin "C1") (pinfunction "IO_L16N_T2_35_C1") (pintype "bidirectional"))
    )
    (net (code "200") (name "unconnected-(U1E-IO_L16P_T2_35-PadC2)") (class "Default")
      (node (ref "U1") (pin "C2") (pinfunction "IO_L16P_T2_35_C2") (pintype "bidirectional"))
    )
    (net (code "201") (name "unconnected-(U1E-IO_L17N_T2_35-PadG1)") (class "Default")
      (node (ref "U1") (pin "G1") (pinfunction "IO_L17N_T2_35_G1") (pintype "bidirectional"))
    )
    (net (code "202") (name "unconnected-(U1E-IO_L17P_T2_35-PadH1)") (class "Default")
      (node (ref "U1") (pin "H1") (pinfunction "IO_L17P_T2_35_H1") (pintype "bidirectional"))
    )
    (net (code "203") (name "unconnected-(U1E-IO_L18N_T2_35-PadE1)") (class "Default")
      (node (ref "U1") (pin "E1") (pinfunction "IO_L18N_T2_35_E1") (pintype "bidirectional"))
    )
    (net (code "204") (name "unconnected-(U1E-IO_L18P_T2_35-PadF1)") (class "Default")
      (node (ref "U1") (pin "F1") (pinfunction "IO_L18P_T2_35_F1") (pintype "bidirectional"))
    )
    (net (code "205") (name "unconnected-(U1E-IO_L19N_T3_VREF_35-PadF6)") (class "Default")
      (node (ref "U1") (pin "F6") (pinfunction "IO_L19N_T3_VREF_35_F6") (pintype "bidirectional"))
    )
    (net (code "206") (name "unconnected-(U1E-IO_L19P_T3_35-PadG6)") (class "Default")
      (node (ref "U1") (pin "G6") (pinfunction "IO_L19P_T3_35_G6") (pintype "bidirectional"))
    )
    (net (code "207") (name "unconnected-(U1E-IO_L20N_T3_35-PadG3)") (class "Default")
      (node (ref "U1") (pin "G3") (pinfunction "IO_L20N_T3_35_G3") (pintype "bidirectional"))
    )
    (net (code "208") (name "unconnected-(U1E-IO_L20P_T3_35-PadG4)") (class "Default")
      (node (ref "U1") (pin "G4") (pinfunction "IO_L20P_T3_35_G4") (pintype "bidirectional"))
    )
    (net (code "209") (name "unconnected-(U1E-IO_L21N_T3_DQS_35-PadH4)") (class "Default")
      (node (ref "U1") (pin "H4") (pinfunction "IO_L21N_T3_DQS_35_H4") (pintype "bidirectional"))
    )
    (net (code "210") (name "unconnected-(U1E-IO_L21P_T3_DQS_35-PadJ4)") (class "Default")
      (node (ref "U1") (pin "J4") (pinfunction "IO_L21P_T3_DQS_35_J4") (pintype "bidirectional"))
    )
    (net (code "211") (name "unconnected-(U1E-IO_L22N_T3_35-PadJ2)") (class "Default")
      (node (ref "U1") (pin "J2") (pinfunction "IO_L22N_T3_35_J2") (pintype "bidirectional"))
    )
    (net (code "212") (name "unconnected-(U1E-IO_L22P_T3_35-PadJ3)") (class "Default")
      (node (ref "U1") (pin "J3") (pinfunction "IO_L22P_T3_35_J3") (pintype "bidirectional"))
    )
    (net (code "213") (name "unconnected-(U1E-IO_L23N_T3_35-PadK1)") (class "Default")
      (node (ref "U1") (pin "K1") (pinfunction "IO_L23N_T3_35_K1") (pintype "bidirectional"))
    )
    (net (code "214") (name "unconnected-(U1E-IO_L23P_T3_35-PadK2)") (class "Default")
      (node (ref "U1") (pin "K2") (pinfunction "IO_L23P_T3_35_K2") (pintype "bidirectional"))
    )
    (net (code "215") (name "unconnected-(U1E-IO_L24N_T3_35-PadH5)") (class "Default")
      (node (ref "U1") (pin "H5") (pinfunction "IO_L24N_T3_35_H5") (pintype "bidirectional"))
    )
    (net (code "216") (name "unconnected-(U1E-IO_L24P_T3_35-PadH6)") (class "Default")
      (node (ref "U1") (pin "H6") (pinfunction "IO_L24P_T3_35_H6") (pintype "bidirectional"))
    )
  )
)
